# Badge.net
KiCad netlist of a schematic drawn in Altium Designer
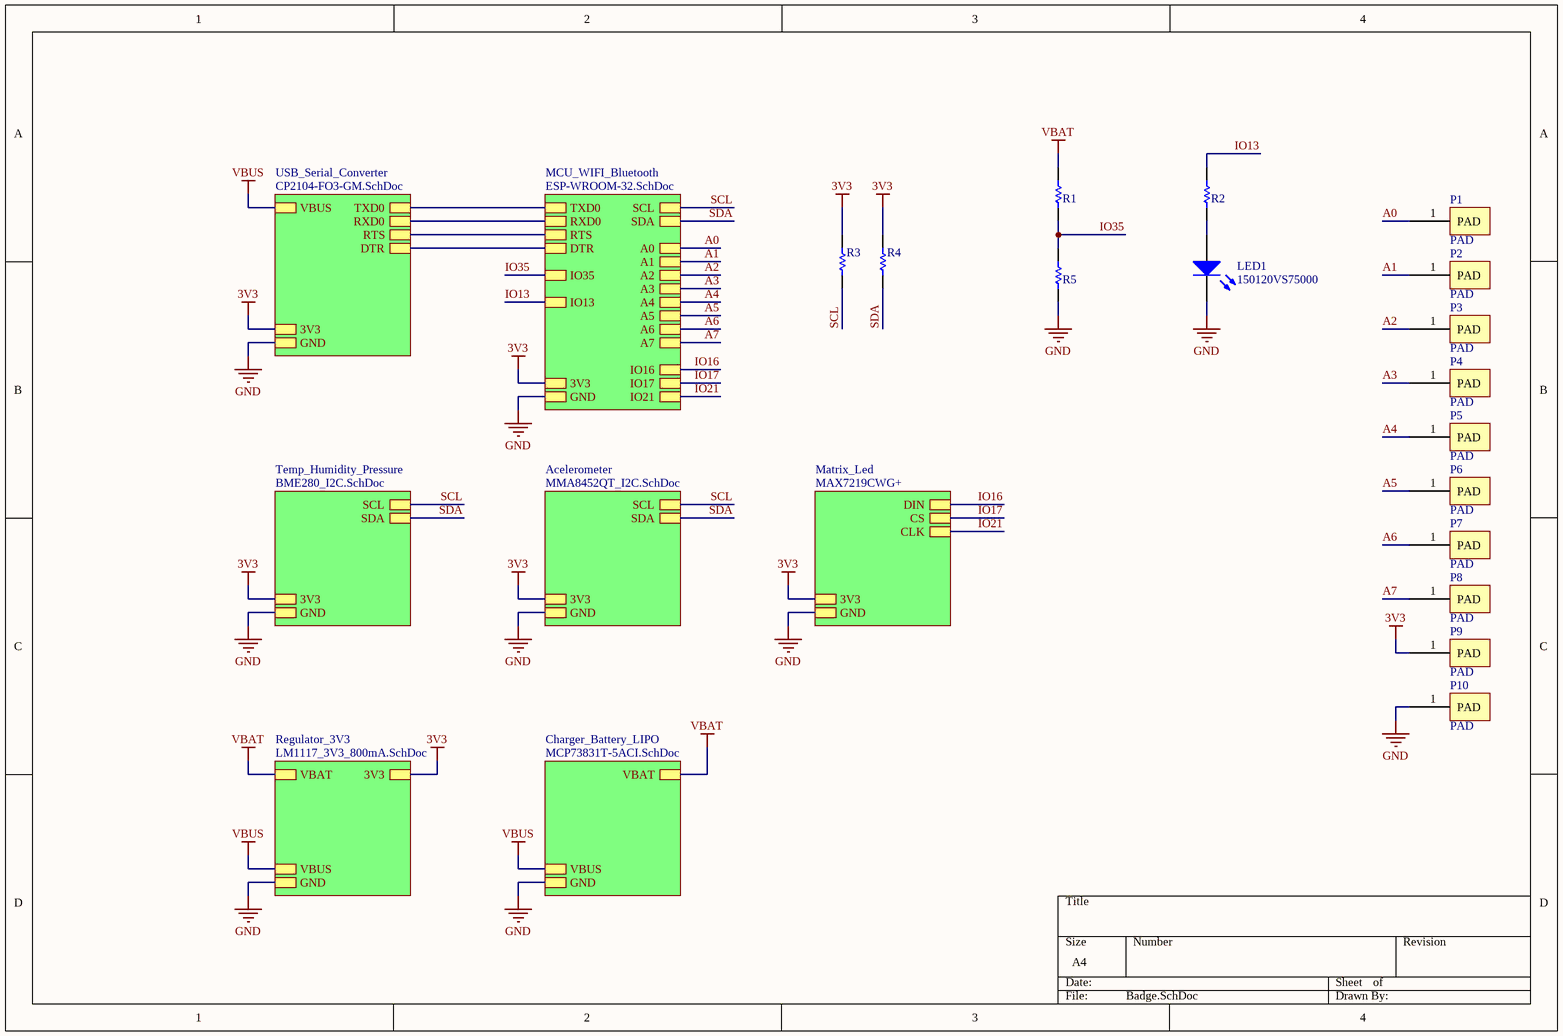
[diagram p0: Badge.SchDoc]

(export (version "E")
  (design (tool "Eeschema 10.0.6"))
  (components
    (comp (ref "LED1")
      (value "150120VS75000")
      (footprint "1206_A")
      (description "SMD mono-color Chip LED, WL-SMCW, Bright Green")
      (fields (field (name "MANUFACTURER") "Wuerth Elektronik"))
      (libsource (lib "Altium Content Vault") (part "WE-LED_K1A2-2"))
    )
    (comp (ref "P1")
      (value "PAD")
      (footprint "Pad_C")
      (description "PAD 2mm")
      (libsource (lib "LIB_FIT") (part "PAD"))
    )
    (comp (ref "P2")
      (value "PAD")
      (footprint "Pad_C")
      (description "PAD 2mm")
      (libsource (lib "LIB_FIT") (part "PAD"))
    )
    (comp (ref "P3")
      (value "PAD")
      (footprint "Pad_C")
      (description "PAD 2mm")
      (libsource (lib "LIB_FIT") (part "PAD"))
    )
    (comp (ref "P4")
      (value "PAD")
      (footprint "Pad_C")
      (description "PAD 2mm")
      (libsource (lib "LIB_FIT") (part "PAD"))
    )
    (comp (ref "P5")
      (value "PAD")
      (footprint "Pad_C")
      (description "PAD 2mm")
      (libsource (lib "LIB_FIT") (part "PAD"))
    )
    (comp (ref "P6")
      (value "PAD")
      (footprint "Pad_C")
      (description "PAD 2mm")
      (libsource (lib "LIB_FIT") (part "PAD"))
    )
    (comp (ref "P7")
      (value "PAD")
      (footprint "Pad_C")
      (description "PAD 2mm")
      (libsource (lib "LIB_FIT") (part "PAD"))
    )
    (comp (ref "P8")
      (value "PAD")
      (footprint "Pad_C")
      (description "PAD 2mm")
      (libsource (lib "LIB_FIT") (part "PAD"))
    )
    (comp (ref "P9")
      (value "PAD")
      (footprint "Pad_C")
      (description "PAD 2mm")
      (libsource (lib "LIB_FIT") (part "PAD"))
    )
    (comp (ref "P10")
      (value "PAD")
      (footprint "Pad_C")
      (description "PAD 2mm")
      (libsource (lib "LIB_FIT") (part "PAD"))
    )
    (comp (ref "R1")
      (value "ERA6AEB104V")
      (footprint "RESC2013X60X40NL20T25")
      (description "100 kOhms ±0.1% 0.125W, 1/8W Chip Resistor 0805 (2012 Metric) Automotive AEC-Q200 Thin Film")
      (fields (field (name "MANUFACTURER") "Panasonic"))
      (libsource (lib "Altium Content Vault") (part "RES"))
    )
    (comp (ref "R2")
      (value "ERJ-P06J102V")
      (footprint "RESC2013X70X40NL20T20")
      (description "RES SMD 1K OHM 5% 1/2W 0805")
      (fields (field (name "MANUFACTURER") "Panasonic"))
      (libsource (lib "Altium Content Vault") (part "RES"))
    )
    (comp (ref "R3")
      (value "RK73B2ATTD103J")
      (footprint "RESC2013X60X30NL20T20")
      (fields (field (name "MANUFACTURER") "KOA Speer"))
      (libsource (lib "Altium Content Vault") (part "RES"))
    )
    (comp (ref "R4")
      (value "RK73B2ATTD103J")
      (footprint "RESC2013X60X30NL20T20")
      (fields (field (name "MANUFACTURER") "KOA Speer"))
      (libsource (lib "Altium Content Vault") (part "RES"))
    )
    (comp (ref "R5")
      (value "ERA6AEB104V")
      (footprint "RESC2013X60X40NL20T25")
      (description "100 kOhms ±0.1% 0.125W, 1/8W Chip Resistor 0805 (2012 Metric) Automotive AEC-Q200 Thin Film")
      (fields (field (name "MANUFACTURER") "Panasonic"))
      (libsource (lib "Altium Content Vault") (part "RES"))
    )
  )
  (nets
    (net (code "1") (name "/A0") (class "Default")
      (node (ref "P1") (pin "1") (pinfunction "PAD_1") (pintype "passive"))
    )
    (net (code "2") (name "/A1") (class "Default")
      (node (ref "P2") (pin "1") (pinfunction "PAD_1") (pintype "passive"))
    )
    (net (code "3") (name "/A2") (class "Default")
      (node (ref "P3") (pin "1") (pinfunction "PAD_1") (pintype "passive"))
    )
    (net (code "4") (name "/A3") (class "Default")
      (node (ref "P4") (pin "1") (pinfunction "PAD_1") (pintype "passive"))
    )
    (net (code "5") (name "/A4") (class "Default")
      (node (ref "P5") (pin "1") (pinfunction "PAD_1") (pintype "passive"))
    )
    (net (code "6") (name "/A5") (class "Default")
      (node (ref "P6") (pin "1") (pinfunction "PAD_1") (pintype "passive"))
    )
    (net (code "7") (name "/A6") (class "Default")
      (node (ref "P7") (pin "1") (pinfunction "PAD_1") (pintype "passive"))
    )
    (net (code "8") (name "/A7") (class "Default")
      (node (ref "P8") (pin "1") (pinfunction "PAD_1") (pintype "passive"))
    )
    (net (code "10") (name "/IO13") (class "Default")
      (node (ref "R2") (pin "2") (pinfunction "2_2") (pintype "passive"))
    )
    (net (code "14") (name "/IO35") (class "Default")
      (node (ref "R1") (pin "1") (pinfunction "1_1") (pintype "passive"))
      (node (ref "R5") (pin "2") (pinfunction "2_2") (pintype "passive"))
    )
    (net (code "17") (name "/SCL") (class "Default")
      (node (ref "R3") (pin "1") (pinfunction "1_1") (pintype "passive"))
    )
    (net (code "18") (name "/SDA") (class "Default")
      (node (ref "R4") (pin "1") (pinfunction "1_1") (pintype "passive"))
    )
    (net (code "20") (name "3V3") (class "Default")
      (node (ref "P9") (pin "1") (pinfunction "PAD_1") (pintype "passive"))
      (node (ref "R3") (pin "2") (pinfunction "2_2") (pintype "passive"))
      (node (ref "R4") (pin "2") (pinfunction "2_2") (pintype "passive"))
    )
    (net (code "21") (name "GND") (class "Default")
      (node (ref "LED1") (pin "1") (pinfunction "K_1") (pintype "passive"))
      (node (ref "P10") (pin "1") (pinfunction "PAD_1") (pintype "passive"))
      (node (ref "R5") (pin "1") (pinfunction "1_1") (pintype "passive"))
    )
    (net (code "22") (name "Net-(LED1-A)") (class "Default")
      (node (ref "LED1") (pin "2") (pinfunction "A_2") (pintype "passive"))
      (node (ref "R2") (pin "1") (pinfunction "1_1") (pintype "passive"))
    )
    (net (code "23") (name "VBAT") (class "Default")
      (node (ref "R1") (pin "2") (pinfunction "2_2") (pintype "passive"))
    )
  )
)
